# powe-board.net
KiCad netlist of a schematic drawn in EAGLE
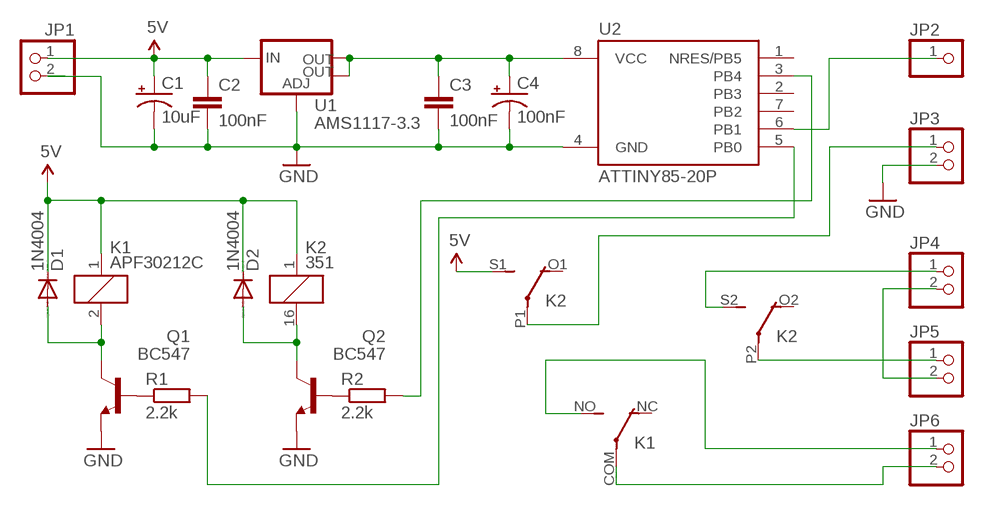
[diagram p0: schematic, sheet 1]

(export (version "E")
  (design (tool "Eeschema 10.0.6"))
  (components
    (comp (ref "C1")
      (value "10uF")
      (footprint "eagle-import:CPOL-RADIAL-10UF-25V-KIT")
      (libsource (lib "eagle-import") (part "10UF-25V-20%(PTH)KIT"))
    )
    (comp (ref "C2")
      (value "100nF")
      (footprint "eagle-import:0402-CAP")
      (libsource (lib "eagle-import") (part "CAP0402-CAP"))
    )
    (comp (ref "C3")
      (value "100nF")
      (footprint "eagle-import:0402-CAP")
      (libsource (lib "eagle-import") (part "CAP0402-CAP"))
    )
    (comp (ref "C4")
      (value "100nF")
      (footprint "eagle-import:CPOL-RADIAL-10UF-25V-KIT")
      (libsource (lib "eagle-import") (part "10UF-25V-20%(PTH)KIT"))
    )
    (comp (ref "D1")
      (value "1N4004")
      (footprint "eagle-import:DO41-10")
      (libsource (lib "eagle-import") (part "1N4004"))
    )
    (comp (ref "D2")
      (value "1N4004")
      (footprint "eagle-import:DO41-10")
      (libsource (lib "eagle-import") (part "1N4004"))
    )
    (comp (ref "JP1")
      (value "PINHD-1X2")
      (footprint "eagle-import:1X02")
      (libsource (lib "eagle-import") (part "PINHD-1X2"))
    )
    (comp (ref "JP2")
      (value "PINHD-1X1")
      (footprint "eagle-import:1X01")
      (libsource (lib "eagle-import") (part "PINHD-1X1"))
    )
    (comp (ref "JP3")
      (value "PINHD-1X2")
      (footprint "eagle-import:1X02")
      (libsource (lib "eagle-import") (part "PINHD-1X2"))
    )
    (comp (ref "JP4")
      (value "PINHD-1X2")
      (footprint "eagle-import:1X02")
      (libsource (lib "eagle-import") (part "PINHD-1X2"))
    )
    (comp (ref "JP5")
      (value "PINHD-1X2")
      (footprint "eagle-import:1X02")
      (libsource (lib "eagle-import") (part "PINHD-1X2"))
    )
    (comp (ref "JP6")
      (value "PINHD-1X2")
      (footprint "eagle-import:1X02")
      (libsource (lib "eagle-import") (part "PINHD-1X2"))
    )
    (comp (ref "K1")
      (value "APF30212C")
      (footprint "eagle-import:APF30212C")
      (libsource (lib "eagle-import") (part "APF30212C"))
    )
    (comp (ref "K2")
      (value "351")
      (footprint "eagle-import:351")
      (libsource (lib "eagle-import") (part "351"))
    )
    (comp (ref "Q1")
      (value "BC547")
      (footprint "eagle-import:TO92")
      (libsource (lib "eagle-import") (part "BC547"))
    )
    (comp (ref "Q2")
      (value "BC547")
      (footprint "eagle-import:TO92")
      (libsource (lib "eagle-import") (part "BC547"))
    )
    (comp (ref "R1")
      (value "2.2k")
      (footprint "eagle-import:0204_7")
      (libsource (lib "eagle-import") (part "R-EU_0204/7"))
    )
    (comp (ref "R2")
      (value "2.2k")
      (footprint "eagle-import:0204_7")
      (libsource (lib "eagle-import") (part "R-EU_0204/7"))
    )
    (comp (ref "U1")
      (value "AMS1117-3.3")
      (footprint "eagle-import:SOT223")
      (libsource (lib "eagle-import") (part "V_REG_LM1117SOT223"))
    )
    (comp (ref "U2")
      (value "ATTINY85-20P")
      (footprint "eagle-import:PDIP08_300MIL")
      (libsource (lib "eagle-import") (part "ATTINY85P-20"))
    )
  )
  (nets
    (net (code "1") (name "5V") (class "Default")
      (node (ref "C1") (pin "1") (pinfunction "+_1") (pintype "passive"))
      (node (ref "C2") (pin "1") (pinfunction "1_1") (pintype "passive"))
      (node (ref "D1") (pin "C") (pinfunction "C_C") (pintype "passive"))
      (node (ref "D2") (pin "C") (pinfunction "C_C") (pintype "passive"))
      (node (ref "JP1") (pin "1") (pinfunction "1_1") (pintype "passive"))
      (node (ref "K1") (pin "1") (pinfunction "1_1") (pintype "passive"))
      (node (ref "K2") (pin "1") (pinfunction "1_1") (pintype "passive"))
      (node (ref "K2") (pin "S1") (pinfunction "S_S1") (pintype "passive"))
      (node (ref "U1") (pin "3") (pinfunction "IN_3") (pintype "input"))
    )
    (net (code "2") (name "GND") (class "Default")
      (node (ref "C1") (pin "2") (pinfunction "-_2") (pintype "passive"))
      (node (ref "C2") (pin "2") (pinfunction "2_2") (pintype "passive"))
      (node (ref "C3") (pin "2") (pinfunction "2_2") (pintype "passive"))
      (node (ref "C4") (pin "2") (pinfunction "-_2") (pintype "passive"))
      (node (ref "JP1") (pin "2") (pinfunction "2_2") (pintype "passive"))
      (node (ref "JP3") (pin "2") (pinfunction "2_2") (pintype "passive"))
      (node (ref "Q1") (pin "1") (pinfunction "E_1") (pintype "passive"))
      (node (ref "Q2") (pin "1") (pinfunction "E_1") (pintype "passive"))
      (node (ref "U1") (pin "1") (pinfunction "ADJ_1") (pintype "input"))
      (node (ref "U2") (pin "4") (pinfunction "GND_4") (pintype "power_in"))
    )
    (net (code "3") (name "Net-(C4-+)") (class "Default")
      (node (ref "C3") (pin "1") (pinfunction "1_1") (pintype "passive"))
      (node (ref "C4") (pin "1") (pinfunction "+_1") (pintype "passive"))
      (node (ref "U1") (pin "2") (pinfunction "OUT_2") (pintype "output"))
      (node (ref "U1") (pin "4") (pinfunction "OUT_4") (pintype "output"))
      (node (ref "U2") (pin "8") (pinfunction "VCC_8") (pintype "power_in"))
    )
    (net (code "4") (name "Net-(JP4-Pad2)") (class "Default")
      (node (ref "JP4") (pin "2") (pinfunction "2_2") (pintype "passive"))
      (node (ref "JP5") (pin "2") (pinfunction "2_2") (pintype "passive"))
    )
    (net (code "5") (name "Net-(K1B-P)") (class "Default")
      (node (ref "JP6") (pin "2") (pinfunction "2_2") (pintype "passive"))
      (node (ref "K1") (pin "COM") (pinfunction "P_COM") (pintype "passive"))
    )
    (net (code "6") (name "Net-(K1B-S)") (class "Default")
      (node (ref "JP6") (pin "1") (pinfunction "1_1") (pintype "passive"))
      (node (ref "K1") (pin "NO") (pinfunction "S_NO") (pintype "passive"))
    )
    (net (code "7") (name "Net-(K2A-2)") (class "Default")
      (node (ref "D2") (pin "A") (pinfunction "A_A") (pintype "passive"))
      (node (ref "K2") (pin "16") (pinfunction "2_16") (pintype "passive"))
      (node (ref "Q2") (pin "3") (pinfunction "C_3") (pintype "passive"))
    )
    (net (code "8") (name "Net-(K2B-P)") (class "Default")
      (node (ref "JP3") (pin "1") (pinfunction "1_1") (pintype "passive"))
      (node (ref "K2") (pin "P1") (pinfunction "P_P1") (pintype "passive"))
    )
    (net (code "9") (name "Net-(K2C-P)") (class "Default")
      (node (ref "JP5") (pin "1") (pinfunction "1_1") (pintype "passive"))
      (node (ref "K2") (pin "P2") (pinfunction "P_P2") (pintype "passive"))
    )
    (net (code "10") (name "Net-(K2C-S)") (class "Default")
      (node (ref "JP4") (pin "1") (pinfunction "1_1") (pintype "passive"))
      (node (ref "K2") (pin "S2") (pinfunction "S_S2") (pintype "passive"))
    )
    (net (code "11") (name "Net-(Q1-B)") (class "Default")
      (node (ref "Q1") (pin "2") (pinfunction "B_2") (pintype "passive"))
      (node (ref "R1") (pin "1") (pinfunction "1_1") (pintype "passive"))
    )
    (net (code "12") (name "Net-(Q1-C)") (class "Default")
      (node (ref "D1") (pin "A") (pinfunction "A_A") (pintype "passive"))
      (node (ref "K1") (pin "2") (pinfunction "2_2") (pintype "passive"))
      (node (ref "Q1") (pin "3") (pinfunction "C_3") (pintype "passive"))
    )
    (net (code "13") (name "Net-(Q2-B)") (class "Default")
      (node (ref "Q2") (pin "2") (pinfunction "B_2") (pintype "passive"))
      (node (ref "R2") (pin "1") (pinfunction "1_1") (pintype "passive"))
    )
    (net (code "14") (name "Net-(U2-PB0)") (class "Default")
      (node (ref "R1") (pin "2") (pinfunction "2_2") (pintype "passive"))
      (node (ref "U2") (pin "5") (pinfunction "PB0_5") (pintype "bidirectional"))
    )
    (net (code "15") (name "Net-(U2-PB1)") (class "Default")
      (node (ref "JP2") (pin "1") (pinfunction "1_1") (pintype "passive"))
      (node (ref "U2") (pin "6") (pinfunction "PB1_6") (pintype "bidirectional"))
    )
    (net (code "16") (name "Net-(U2-PB4)") (class "Default")
      (node (ref "R2") (pin "2") (pinfunction "2_2") (pintype "passive"))
      (node (ref "U2") (pin "3") (pinfunction "PB4_3") (pintype "bidirectional"))
    )
    (net (code "17") (name "unconnected-(K1B-O-PadNC)") (class "Default")
      (node (ref "K1") (pin "NC") (pinfunction "O_NC") (pintype "passive"))
    )
    (net (code "18") (name "unconnected-(K2B-O-PadO1)") (class "Default")
      (node (ref "K2") (pin "O1") (pinfunction "O_O1") (pintype "passive"))
    )
    (net (code "19") (name "unconnected-(K2C-O-PadO2)") (class "Default")
      (node (ref "K2") (pin "O2") (pinfunction "O_O2") (pintype "passive"))
    )
    (net (code "20") (name "unconnected-(U2-NRES{slash}PB5-Pad1)") (class "Default")
      (node (ref "U2") (pin "1") (pinfunction "NRES/PB5_1") (pintype "bidirectional"))
    )
    (net (code "21") (name "unconnected-(U2-PB2-Pad7)") (class "Default")
      (node (ref "U2") (pin "7") (pinfunction "PB2_7") (pintype "bidirectional"))
    )
    (net (code "22") (name "unconnected-(U2-PB3-Pad2)") (class "Default")
      (node (ref "U2") (pin "2") (pinfunction "PB3_2") (pintype "bidirectional"))
    )
  )
)
